# Cricket_Re.net
KiCad netlist of a schematic drawn in EAGLE
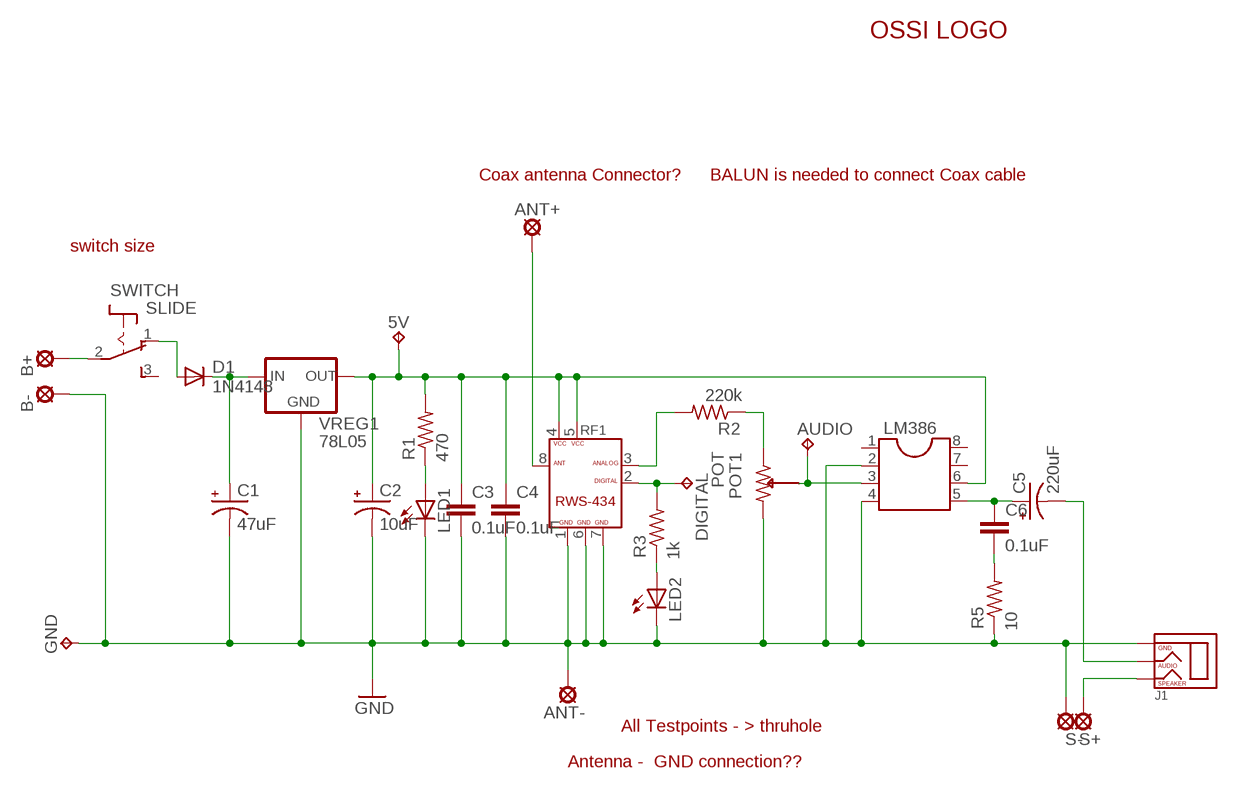
[diagram p0: schematic, sheet 1]

(export (version "E")
  (design (tool "Eeschema 10.0.6"))
  (components
    (comp (ref "5V")
      (value "TPB1,27")
      (footprint "eagle-import:B1,27")
      (libsource (lib "eagle-import") (part "TPB1,27"))
    )
    (comp (ref "ANT+")
      (value "FIXPAD")
      (footprint "eagle-import:FIXPAD")
      (libsource (lib "eagle-import") (part "FIXPAD"))
    )
    (comp (ref "ANT-")
      (value "FIXPAD")
      (footprint "eagle-import:FIXPAD")
      (libsource (lib "eagle-import") (part "FIXPAD"))
    )
    (comp (ref "AUDIO")
      (value "TPB1,27")
      (footprint "eagle-import:B1,27")
      (libsource (lib "eagle-import") (part "TPB1,27"))
    )
    (comp (ref "B+")
      (value "FIXPAD")
      (footprint "eagle-import:FIXPAD")
      (libsource (lib "eagle-import") (part "FIXPAD"))
    )
    (comp (ref "B-")
      (value "FIXPAD")
      (footprint "eagle-import:FIXPAD")
      (libsource (lib "eagle-import") (part "FIXPAD"))
    )
    (comp (ref "C1")
      (value "47uF")
      (footprint "eagle-import:CAPACITOR_POL")
      (libsource (lib "eagle-import") (part "CAPACITOR_POLR5"))
    )
    (comp (ref "C2")
      (value "10uF")
      (footprint "eagle-import:CAPACITOR_POL")
      (libsource (lib "eagle-import") (part "CAPACITOR_POLR5"))
    )
    (comp (ref "C3")
      (value "0.1uF")
      (footprint "eagle-import:CAPACITOR")
      (libsource (lib "eagle-import") (part "CAPACITOR"))
    )
    (comp (ref "C4")
      (value "0.1uF")
      (footprint "eagle-import:CAPACITOR")
      (libsource (lib "eagle-import") (part "CAPACITOR"))
    )
    (comp (ref "C5")
      (value "220uF")
      (footprint "eagle-import:CAPACITOR_POL_R10")
      (libsource (lib "eagle-import") (part "CAPACITOR_POLR10"))
    )
    (comp (ref "C6")
      (value "0.1uF")
      (footprint "eagle-import:CAPACITOR")
      (libsource (lib "eagle-import") (part "CAPACITOR"))
    )
    (comp (ref "D1")
      (value "1N4148")
      (footprint "eagle-import:1N4148")
      (libsource (lib "eagle-import") (part "1N4148"))
    )
    (comp (ref "DIGITAL")
      (value "TPB1,27")
      (footprint "eagle-import:B1,27")
      (libsource (lib "eagle-import") (part "TPB1,27"))
    )
    (comp (ref "GND")
      (value "TPB1,27")
      (footprint "eagle-import:B1,27")
      (libsource (lib "eagle-import") (part "TPB1,27"))
    )
    (comp (ref "J1")
      (value "AUDIOJACK")
      (footprint "eagle-import:AUDIOJACK")
      (libsource (lib "eagle-import") (part "AUDIOJACK"))
    )
    (comp (ref "LED1")
      (value "LED")
      (footprint "eagle-import:LED")
      (libsource (lib "eagle-import") (part "LED"))
    )
    (comp (ref "LED2")
      (value "LED")
      (footprint "eagle-import:LED")
      (libsource (lib "eagle-import") (part "LED"))
    )
    (comp (ref "LM386")
      (value "DIL8")
      (footprint "eagle-import:DIL08")
      (libsource (lib "eagle-import") (part "DIL8"))
    )
    (comp (ref "POT1")
      (value "POT")
      (footprint "eagle-import:POT")
      (libsource (lib "eagle-import") (part "POT"))
    )
    (comp (ref "R1")
      (value "470")
      (footprint "eagle-import:RESISTOR")
      (libsource (lib "eagle-import") (part "RESISTOR"))
    )
    (comp (ref "R2")
      (value "220k")
      (footprint "eagle-import:RESISTOR")
      (libsource (lib "eagle-import") (part "RESISTOR"))
    )
    (comp (ref "R3")
      (value "1k")
      (footprint "eagle-import:RESISTOR")
      (libsource (lib "eagle-import") (part "RESISTOR"))
    )
    (comp (ref "R5")
      (value "10")
      (footprint "eagle-import:RESISTOR")
      (libsource (lib "eagle-import") (part "RESISTOR"))
    )
    (comp (ref "RF1")
      (value "RWS-434")
      (footprint "eagle-import:RWS-434")
      (libsource (lib "eagle-import") (part "RWS-434"))
    )
    (comp (ref "S+")
      (value "FIXPAD")
      (footprint "eagle-import:FIXPAD")
      (libsource (lib "eagle-import") (part "FIXPAD"))
    )
    (comp (ref "S-")
      (value "FIXPAD")
      (footprint "eagle-import:FIXPAD")
      (libsource (lib "eagle-import") (part "FIXPAD"))
    )
    (comp (ref "SWITCH")
      (value "SLIDE")
      (footprint "eagle-import:SLIDE")
      (libsource (lib "eagle-import") (part "SLIDE"))
    )
    (comp (ref "U$1")
      (value "OSSILOGO-10")
      (footprint "eagle-import:OSSILOGO1010")
      (libsource (lib "eagle-import") (part "OSSILOGO-10"))
    )
    (comp (ref "VREG1")
      (value "78L05")
      (footprint "eagle-import:78L05")
      (libsource (lib "eagle-import") (part "78L05"))
    )
  )
  (nets
    (net (code "1") (name "GND") (class "Default")
      (node (ref "ANT-") (pin "P$1") (pinfunction "MP_P$1") (pintype "passive"))
      (node (ref "B-") (pin "P$1") (pinfunction "MP_P$1") (pintype "passive"))
      (node (ref "C1") (pin "-") (pinfunction "2_-") (pintype "passive"))
      (node (ref "C2") (pin "-") (pinfunction "2_-") (pintype "passive"))
      (node (ref "C3") (pin "P$2") (pinfunction "2_P$2") (pintype "passive"))
      (node (ref "C4") (pin "P$2") (pinfunction "2_P$2") (pintype "passive"))
      (node (ref "GND") (pin "PP") (pinfunction "TP_PP") (pintype "input"))
      (node (ref "J1") (pin "G") (pinfunction "GND_G") (pintype "bidirectional"))
      (node (ref "LED1") (pin "C") (pinfunction "C_C") (pintype "passive"))
      (node (ref "LED2") (pin "C") (pinfunction "C_C") (pintype "passive"))
      (node (ref "LM386") (pin "2") (pinfunction "2_2") (pintype "passive"))
      (node (ref "LM386") (pin "4") (pinfunction "4_4") (pintype "passive"))
      (node (ref "POT1") (pin "2") (pinfunction "2_2") (pintype "passive"))
      (node (ref "R5") (pin "P$1") (pinfunction "1_P$1") (pintype "passive"))
      (node (ref "RF1") (pin "1") (pinfunction "1_1") (pintype "bidirectional"))
      (node (ref "RF1") (pin "6") (pinfunction "6_6") (pintype "bidirectional"))
      (node (ref "RF1") (pin "7") (pinfunction "7_7") (pintype "bidirectional"))
      (node (ref "S-") (pin "P$1") (pinfunction "MP_P$1") (pintype "passive"))
      (node (ref "VREG1") (pin "G") (pinfunction "GND_G") (pintype "input"))
    )
    (net (code "2") (name "Net-(5V-TP)") (class "Default")
      (node (ref "5V") (pin "PP") (pinfunction "TP_PP") (pintype "input"))
      (node (ref "C2") (pin "+") (pinfunction "1_+") (pintype "passive"))
      (node (ref "C3") (pin "P$1") (pinfunction "1_P$1") (pintype "passive"))
      (node (ref "C4") (pin "P$1") (pinfunction "1_P$1") (pintype "passive"))
      (node (ref "LM386") (pin "6") (pinfunction "6_6") (pintype "passive"))
      (node (ref "R1") (pin "P$2") (pinfunction "2_P$2") (pintype "passive"))
      (node (ref "RF1") (pin "4") (pinfunction "4_4") (pintype "bidirectional"))
      (node (ref "RF1") (pin "5") (pinfunction "5_5") (pintype "bidirectional"))
      (node (ref "VREG1") (pin "O") (pinfunction "OUT_O") (pintype "passive"))
    )
    (net (code "3") (name "Net-(ANT+-MP)") (class "Default")
      (node (ref "ANT+") (pin "P$1") (pinfunction "MP_P$1") (pintype "passive"))
      (node (ref "RF1") (pin "8") (pinfunction "8_8") (pintype "bidirectional"))
    )
    (net (code "4") (name "Net-(AUDIO-TP)") (class "Default")
      (node (ref "AUDIO") (pin "PP") (pinfunction "TP_PP") (pintype "input"))
      (node (ref "LM386") (pin "3") (pinfunction "3_3") (pintype "passive"))
      (node (ref "POT1") (pin "C") (pinfunction "CENTER_C") (pintype "bidirectional"))
    )
    (net (code "5") (name "Net-(B+-MP)") (class "Default")
      (node (ref "B+") (pin "P$1") (pinfunction "MP_P$1") (pintype "passive"))
      (node (ref "SWITCH") (pin "2") (pinfunction "P_2") (pintype "passive"))
    )
    (net (code "6") (name "Net-(C1-1)") (class "Default")
      (node (ref "C1") (pin "+") (pinfunction "1_+") (pintype "passive"))
      (node (ref "D1") (pin "C") (pinfunction "C_C") (pintype "passive"))
      (node (ref "VREG1") (pin "I") (pinfunction "IN_I") (pintype "input"))
    )
    (net (code "7") (name "Net-(C5-1)") (class "Default")
      (node (ref "C5") (pin "+") (pinfunction "1_+") (pintype "passive"))
      (node (ref "C6") (pin "P$1") (pinfunction "1_P$1") (pintype "passive"))
      (node (ref "LM386") (pin "5") (pinfunction "5_5") (pintype "passive"))
    )
    (net (code "8") (name "Net-(C5-2)") (class "Default")
      (node (ref "C5") (pin "-") (pinfunction "2_-") (pintype "passive"))
      (node (ref "J1") (pin "A") (pinfunction "AUDIO_A") (pintype "bidirectional"))
    )
    (net (code "9") (name "Net-(C6-2)") (class "Default")
      (node (ref "C6") (pin "P$2") (pinfunction "2_P$2") (pintype "passive"))
      (node (ref "R5") (pin "P$2") (pinfunction "2_P$2") (pintype "passive"))
    )
    (net (code "10") (name "Net-(DIGITAL-TP)") (class "Default")
      (node (ref "DIGITAL") (pin "PP") (pinfunction "TP_PP") (pintype "input"))
      (node (ref "R3") (pin "P$2") (pinfunction "2_P$2") (pintype "passive"))
      (node (ref "RF1") (pin "2") (pinfunction "2_2") (pintype "bidirectional"))
    )
    (net (code "11") (name "Net-(J1-SPEAKER)") (class "Default")
      (node (ref "J1") (pin "S") (pinfunction "SPEAKER_S") (pintype "bidirectional"))
      (node (ref "S+") (pin "P$1") (pinfunction "MP_P$1") (pintype "passive"))
    )
    (net (code "12") (name "Net-(R1-1)") (class "Default")
      (node (ref "LED1") (pin "A") (pinfunction "A_A") (pintype "passive"))
      (node (ref "R1") (pin "P$1") (pinfunction "1_P$1") (pintype "passive"))
    )
    (net (code "13") (name "Net-(R2-1)") (class "Default")
      (node (ref "POT1") (pin "1") (pinfunction "1_1") (pintype "passive"))
      (node (ref "R2") (pin "P$1") (pinfunction "1_P$1") (pintype "passive"))
    )
    (net (code "14") (name "Net-(R2-2)") (class "Default")
      (node (ref "R2") (pin "P$2") (pinfunction "2_P$2") (pintype "passive"))
      (node (ref "RF1") (pin "3") (pinfunction "3_3") (pintype "bidirectional"))
    )
    (net (code "15") (name "Net-(R3-1)") (class "Default")
      (node (ref "LED2") (pin "A") (pinfunction "A_A") (pintype "passive"))
      (node (ref "R3") (pin "P$1") (pinfunction "1_P$1") (pintype "passive"))
    )
    (net (code "16") (name "Net-(SWITCH-O)") (class "Default")
      (node (ref "D1") (pin "A") (pinfunction "A_A") (pintype "passive"))
      (node (ref "SWITCH") (pin "1") (pinfunction "O_1") (pintype "passive"))
    )
    (net (code "17") (name "unconnected-(LM386-Pad1)") (class "Default")
      (node (ref "LM386") (pin "1") (pinfunction "1_1") (pintype "passive"))
    )
    (net (code "18") (name "unconnected-(LM386-Pad7)") (class "Default")
      (node (ref "LM386") (pin "7") (pinfunction "7_7") (pintype "passive"))
    )
    (net (code "19") (name "unconnected-(LM386-Pad8)") (class "Default")
      (node (ref "LM386") (pin "8") (pinfunction "8_8") (pintype "passive"))
    )
    (net (code "20") (name "unconnected-(SWITCH-S-Pad3)") (class "Default")
      (node (ref "SWITCH") (pin "3") (pinfunction "S_3") (pintype "passive"))
    )
  )
)
